# 48-24.net
KiCad netlist of a schematic drawn in EasyEDA Pro
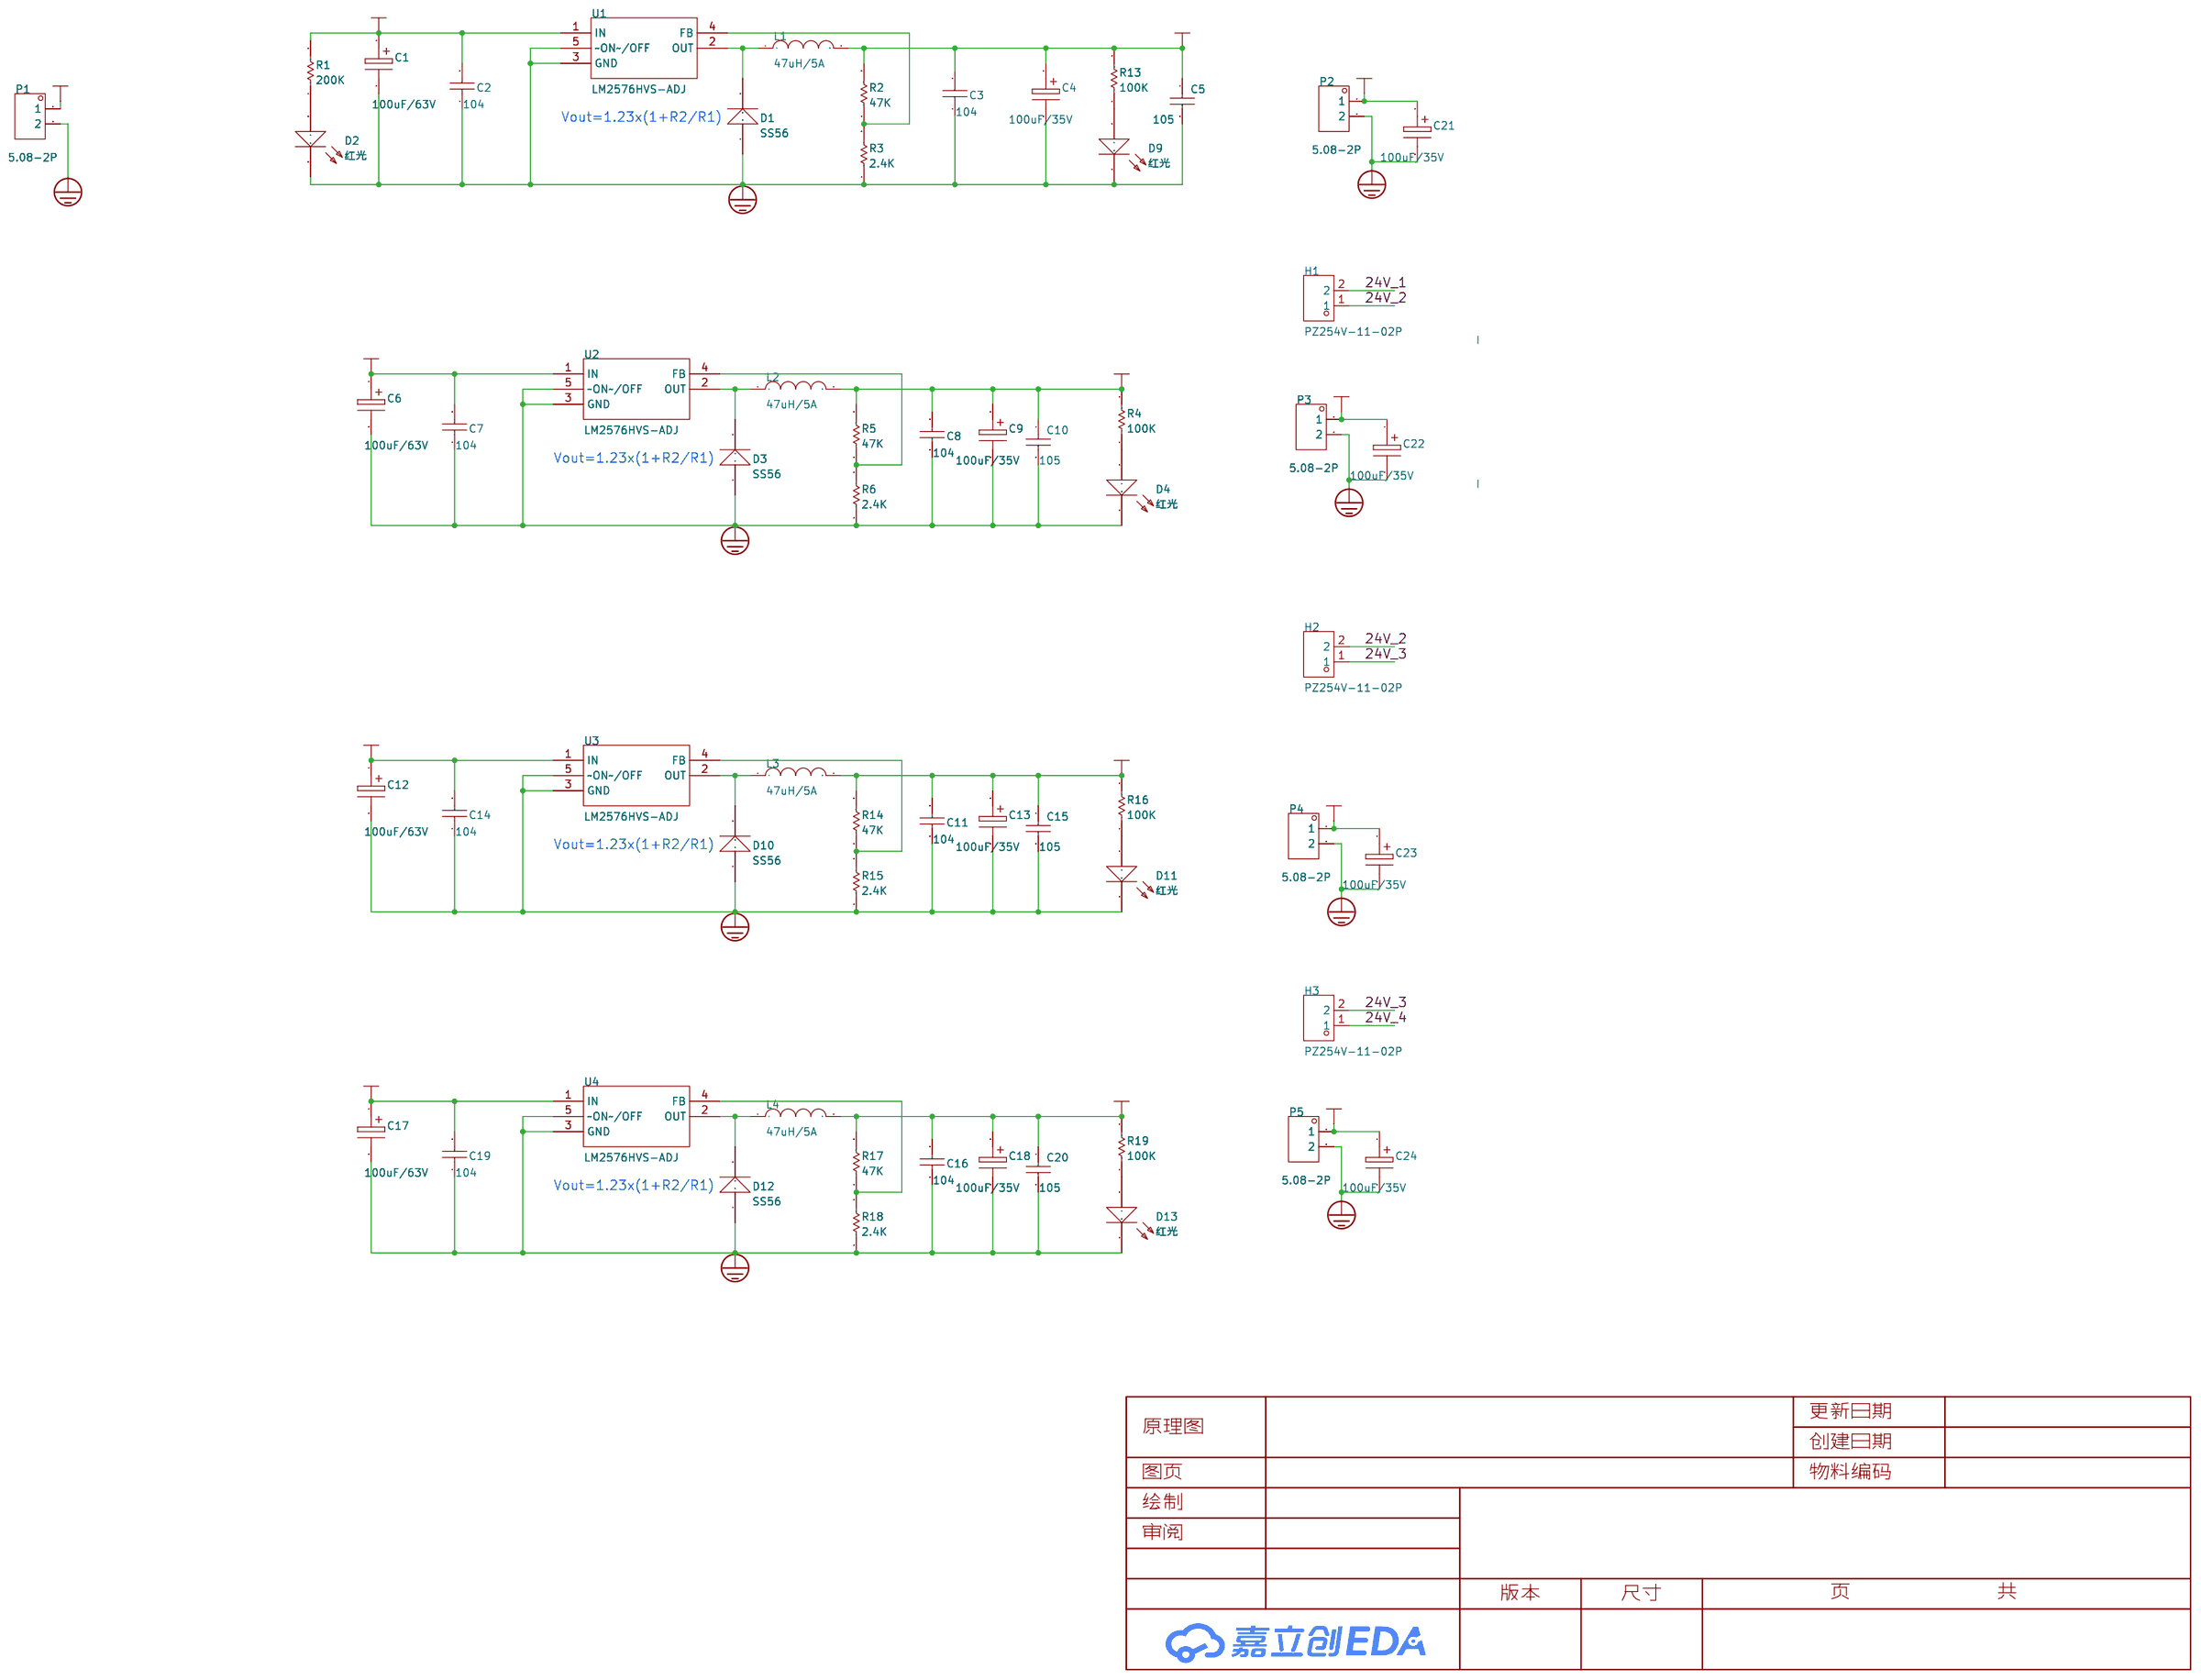
[diagram p0: schematic sheet]

(export (version "E")
  (design (tool "Eeschema 10.0.6"))
  (components
    (comp (ref "C1")
      (value "100uF/63V")
      (footprint "easyedapro:电解电容贴片10x10")
      (libsource (lib "easyedapro") (part "ELECTRO1"))
    )
    (comp (ref "C2")
      (value "104")
      (footprint "easyedapro:电解电容贴片6X6")
      (libsource (lib "easyedapro") (part "CAP"))
    )
    (comp (ref "C3")
      (value "104")
      (footprint "easyedapro:电解电容贴片6X6")
      (libsource (lib "easyedapro") (part "CAP"))
    )
    (comp (ref "C4")
      (value "100uF/35V")
      (footprint "easyedapro:电解电容贴片10x10")
      (libsource (lib "easyedapro") (part "ELECTRO1"))
    )
    (comp (ref "C5")
      (value "105")
      (footprint "easyedapro:电解电容贴片6X6")
      (libsource (lib "easyedapro") (part "CAP"))
    )
    (comp (ref "C6")
      (value "100uF/63V")
      (footprint "easyedapro:电解电容贴片10x10")
      (libsource (lib "easyedapro") (part "ELECTRO1"))
    )
    (comp (ref "C7")
      (value "104")
      (footprint "easyedapro:电解电容贴片6X6")
      (libsource (lib "easyedapro") (part "CAP"))
    )
    (comp (ref "C8")
      (value "104")
      (footprint "easyedapro:电解电容贴片6X6")
      (libsource (lib "easyedapro") (part "CAP"))
    )
    (comp (ref "C9")
      (value "100uF/35V")
      (footprint "easyedapro:电解电容贴片10x10")
      (libsource (lib "easyedapro") (part "ELECTRO1"))
    )
    (comp (ref "C10")
      (value "105")
      (footprint "easyedapro:电解电容贴片6X6")
      (libsource (lib "easyedapro") (part "CAP"))
    )
    (comp (ref "C11")
      (value "104")
      (footprint "easyedapro:电解电容贴片6X6")
      (libsource (lib "easyedapro") (part "CAP"))
    )
    (comp (ref "C12")
      (value "100uF/63V")
      (footprint "easyedapro:电解电容贴片10x10")
      (libsource (lib "easyedapro") (part "ELECTRO1"))
    )
    (comp (ref "C13")
      (value "100uF/35V")
      (footprint "easyedapro:电解电容贴片10x10")
      (libsource (lib "easyedapro") (part "ELECTRO1"))
    )
    (comp (ref "C14")
      (value "104")
      (footprint "easyedapro:电解电容贴片6X6")
      (libsource (lib "easyedapro") (part "CAP"))
    )
    (comp (ref "C15")
      (value "105")
      (footprint "easyedapro:电解电容贴片6X6")
      (libsource (lib "easyedapro") (part "CAP"))
    )
    (comp (ref "C16")
      (value "104")
      (footprint "easyedapro:电解电容贴片6X6")
      (libsource (lib "easyedapro") (part "CAP"))
    )
    (comp (ref "C17")
      (value "100uF/63V")
      (footprint "easyedapro:电解电容贴片10x10")
      (libsource (lib "easyedapro") (part "ELECTRO1"))
    )
    (comp (ref "C18")
      (value "100uF/35V")
      (footprint "easyedapro:电解电容贴片10x10")
      (libsource (lib "easyedapro") (part "ELECTRO1"))
    )
    (comp (ref "C19")
      (value "104")
      (footprint "easyedapro:电解电容贴片6X6")
      (libsource (lib "easyedapro") (part "CAP"))
    )
    (comp (ref "C20")
      (value "105")
      (footprint "easyedapro:电解电容贴片6X6")
      (libsource (lib "easyedapro") (part "CAP"))
    )
    (comp (ref "C21")
      (value "100uF/35V")
      (footprint "easyedapro:电解电容贴片10x10")
      (libsource (lib "easyedapro") (part "ELECTRO1"))
    )
    (comp (ref "C22")
      (value "100uF/35V")
      (footprint "easyedapro:电解电容贴片10x10")
      (libsource (lib "easyedapro") (part "ELECTRO1"))
    )
    (comp (ref "C23")
      (value "100uF/35V")
      (footprint "easyedapro:电解电容贴片10x10")
      (libsource (lib "easyedapro") (part "ELECTRO1"))
    )
    (comp (ref "C24")
      (value "100uF/35V")
      (footprint "easyedapro:电解电容贴片10x10")
      (libsource (lib "easyedapro") (part "ELECTRO1"))
    )
    (comp (ref "D1")
      (value "SS56")
      (footprint "easyedapro:SMA")
      (libsource (lib "easyedapro") (part "1N4148"))
    )
    (comp (ref "D2")
      (value "红光")
      (footprint "easyedapro:0603LED")
      (libsource (lib "easyedapro") (part "LED"))
    )
    (comp (ref "D3")
      (value "SS56")
      (footprint "easyedapro:SMA")
      (libsource (lib "easyedapro") (part "1N4148"))
    )
    (comp (ref "D4")
      (value "红光")
      (footprint "easyedapro:0603LED")
      (libsource (lib "easyedapro") (part "LED"))
    )
    (comp (ref "D9")
      (value "红光")
      (footprint "easyedapro:0603LED")
      (libsource (lib "easyedapro") (part "LED"))
    )
    (comp (ref "D10")
      (value "SS56")
      (footprint "easyedapro:SMA")
      (libsource (lib "easyedapro") (part "1N4148"))
    )
    (comp (ref "D11")
      (value "红光")
      (footprint "easyedapro:0603LED")
      (libsource (lib "easyedapro") (part "LED"))
    )
    (comp (ref "D12")
      (value "SS56")
      (footprint "easyedapro:SMA")
      (libsource (lib "easyedapro") (part "1N4148"))
    )
    (comp (ref "D13")
      (value "红光")
      (footprint "easyedapro:0603LED")
      (libsource (lib "easyedapro") (part "LED"))
    )
    (comp (ref "H1")
      (value "PZ254V-11-02P")
      (footprint "easyedapro:HDR-TH_2P-P2.54-V-M")
      (fields (field (name "Manufacturer") "XFCN(兴飞)"))
      (libsource (lib "easyedapro") (part "PZ254V-11-02P"))
    )
    (comp (ref "H2")
      (value "PZ254V-11-02P")
      (footprint "easyedapro:HDR-TH_2P-P2.54-V-M")
      (fields (field (name "Manufacturer") "XFCN(兴飞)"))
      (libsource (lib "easyedapro") (part "PZ254V-11-02P"))
    )
    (comp (ref "H3")
      (value "PZ254V-11-02P")
      (footprint "easyedapro:HDR-TH_2P-P2.54-V-M")
      (fields (field (name "Manufacturer") "XFCN(兴飞)"))
      (libsource (lib "easyedapro") (part "PZ254V-11-02P"))
    )
    (comp (ref "L1")
      (value "47uH/5A")
      (footprint "easyedapro:IND-SMD_L13.45-W12.6")
      (description "Inductor")
      (libsource (lib "easyedapro") (part "Inductor"))
    )
    (comp (ref "L2")
      (value "47uH/5A")
      (footprint "easyedapro:IND-SMD_L13.45-W12.6")
      (description "Inductor")
      (libsource (lib "easyedapro") (part "Inductor"))
    )
    (comp (ref "L3")
      (value "47uH/5A")
      (footprint "easyedapro:IND-SMD_L13.45-W12.6")
      (description "Inductor")
      (libsource (lib "easyedapro") (part "Inductor"))
    )
    (comp (ref "L4")
      (value "47uH/5A")
      (footprint "easyedapro:IND-SMD_L13.45-W12.6")
      (description "Inductor")
      (libsource (lib "easyedapro") (part "Inductor"))
    )
    (comp (ref "P1")
      (value "5.08-2P")
      (footprint "easyedapro:CONN-TH_WJ2EDGVC-5.08-2P")
      (fields (field (name "Manufacturer") "KANGNEX(康奈克斯电气)"))
      (libsource (lib "easyedapro") (part "WJ2EDGVC-5.08-2P"))
    )
    (comp (ref "P2")
      (value "5.08-2P")
      (footprint "easyedapro:CONN-TH_WJ2EDGVC-5.08-2P")
      (fields (field (name "Manufacturer") "KANGNEX(康奈克斯电气)"))
      (libsource (lib "easyedapro") (part "WJ2EDGVC-5.08-2P"))
    )
    (comp (ref "P3")
      (value "5.08-2P")
      (footprint "easyedapro:CONN-TH_WJ2EDGVC-5.08-2P")
      (fields (field (name "Manufacturer") "KANGNEX(康奈克斯电气)"))
      (libsource (lib "easyedapro") (part "WJ2EDGVC-5.08-2P"))
    )
    (comp (ref "P4")
      (value "5.08-2P")
      (footprint "easyedapro:CONN-TH_WJ2EDGVC-5.08-2P")
      (fields (field (name "Manufacturer") "KANGNEX(康奈克斯电气)"))
      (libsource (lib "easyedapro") (part "WJ2EDGVC-5.08-2P"))
    )
    (comp (ref "P5")
      (value "5.08-2P")
      (footprint "easyedapro:CONN-TH_WJ2EDGVC-5.08-2P")
      (fields (field (name "Manufacturer") "KANGNEX(康奈克斯电气)"))
      (libsource (lib "easyedapro") (part "WJ2EDGVC-5.08-2P"))
    )
    (comp (ref "R1")
      (value "10K")
      (footprint "easyedapro:0603R")
      (description "Resistor")
      (libsource (lib "easyedapro") (part "RES"))
    )
    (comp (ref "R2")
      (value "47K")
      (footprint "easyedapro:0603R")
      (description "Resistor")
      (libsource (lib "easyedapro") (part "RES"))
    )
    (comp (ref "R3")
      (value "2.4K")
      (footprint "easyedapro:0603R")
      (description "Resistor")
      (libsource (lib "easyedapro") (part "RES"))
    )
    (comp (ref "R4")
      (value "10K")
      (footprint "easyedapro:0603R")
      (description "Resistor")
      (libsource (lib "easyedapro") (part "RES"))
    )
    (comp (ref "R5")
      (value "47K")
      (footprint "easyedapro:0603R")
      (description "Resistor")
      (libsource (lib "easyedapro") (part "RES"))
    )
    (comp (ref "R6")
      (value "2.4K")
      (footprint "easyedapro:0603R")
      (description "Resistor")
      (libsource (lib "easyedapro") (part "RES"))
    )
    (comp (ref "R13")
      (value "10K")
      (footprint "easyedapro:0603R")
      (description "Resistor")
      (libsource (lib "easyedapro") (part "RES"))
    )
    (comp (ref "R14")
      (value "47K")
      (footprint "easyedapro:0603R")
      (description "Resistor")
      (libsource (lib "easyedapro") (part "RES"))
    )
    (comp (ref "R15")
      (value "2.4K")
      (footprint "easyedapro:0603R")
      (description "Resistor")
      (libsource (lib "easyedapro") (part "RES"))
    )
    (comp (ref "R16")
      (value "10K")
      (footprint "easyedapro:0603R")
      (description "Resistor")
      (libsource (lib "easyedapro") (part "RES"))
    )
    (comp (ref "R17")
      (value "47K")
      (footprint "easyedapro:0603R")
      (description "Resistor")
      (libsource (lib "easyedapro") (part "RES"))
    )
    (comp (ref "R18")
      (value "2.4K")
      (footprint "easyedapro:0603R")
      (description "Resistor")
      (libsource (lib "easyedapro") (part "RES"))
    )
    (comp (ref "R19")
      (value "10K")
      (footprint "easyedapro:0603R")
      (description "Resistor")
      (libsource (lib "easyedapro") (part "RES"))
    )
    (comp (ref "U1")
      (value "LM2576HVS-ADJ")
      (footprint "easyedapro:TO-263")
      (description "Simple Switcher 3A Step Down Voltage Regulator")
      (libsource (lib "easyedapro") (part "LM2576S-5.0"))
    )
    (comp (ref "U2")
      (value "LM2576HVS-ADJ")
      (footprint "easyedapro:TO-263")
      (description "Simple Switcher 3A Step Down Voltage Regulator")
      (libsource (lib "easyedapro") (part "LM2576S-5.0"))
    )
    (comp (ref "U3")
      (value "LM2576HVS-ADJ")
      (footprint "easyedapro:TO-263")
      (description "Simple Switcher 3A Step Down Voltage Regulator")
      (libsource (lib "easyedapro") (part "LM2576S-5.0"))
    )
    (comp (ref "U4")
      (value "LM2576HVS-ADJ")
      (footprint "easyedapro:TO-263")
      (description "Simple Switcher 3A Step Down Voltage Regulator")
      (libsource (lib "easyedapro") (part "LM2576S-5.0"))
    )
  )
  (nets
    (net (code "1") (name "24V_1") (class "Default")
      (node (ref "C21") (pin "1") (pintype "unspecified"))
      (node (ref "C3") (pin "2") (pinfunction "2_2") (pintype "unspecified"))
      (node (ref "C4") (pin "1") (pintype "unspecified"))
      (node (ref "C5") (pin "1") (pinfunction "1_1") (pintype "unspecified"))
      (node (ref "H1") (pin "2") (pinfunction "2_2") (pintype "unspecified"))
      (node (ref "L1") (pin "2") (pinfunction "2_2") (pintype "unspecified"))
      (node (ref "P2") (pin "1") (pinfunction "1_1") (pintype "unspecified"))
      (node (ref "R13") (pin "2") (pinfunction "2_2") (pintype "unspecified"))
      (node (ref "R2") (pin "2") (pinfunction "2_2") (pintype "unspecified"))
    )
    (net (code "2") (name "24V_2") (class "Default")
      (node (ref "C10") (pin "1") (pinfunction "1_1") (pintype "unspecified"))
      (node (ref "C22") (pin "1") (pintype "unspecified"))
      (node (ref "C8") (pin "2") (pinfunction "2_2") (pintype "unspecified"))
      (node (ref "C9") (pin "1") (pintype "unspecified"))
      (node (ref "H1") (pin "1") (pinfunction "1_1") (pintype "unspecified"))
      (node (ref "H2") (pin "2") (pinfunction "2_2") (pintype "unspecified"))
      (node (ref "L2") (pin "2") (pinfunction "2_2") (pintype "unspecified"))
      (node (ref "P3") (pin "1") (pinfunction "1_1") (pintype "unspecified"))
      (node (ref "R4") (pin "2") (pinfunction "2_2") (pintype "unspecified"))
      (node (ref "R5") (pin "2") (pinfunction "2_2") (pintype "unspecified"))
    )
    (net (code "3") (name "24V_3") (class "Default")
      (node (ref "C11") (pin "2") (pinfunction "2_2") (pintype "unspecified"))
      (node (ref "C13") (pin "1") (pintype "unspecified"))
      (node (ref "C15") (pin "1") (pinfunction "1_1") (pintype "unspecified"))
      (node (ref "C23") (pin "1") (pintype "unspecified"))
      (node (ref "H2") (pin "1") (pinfunction "1_1") (pintype "unspecified"))
      (node (ref "H3") (pin "2") (pinfunction "2_2") (pintype "unspecified"))
      (node (ref "L3") (pin "2") (pinfunction "2_2") (pintype "unspecified"))
      (node (ref "P4") (pin "1") (pinfunction "1_1") (pintype "unspecified"))
      (node (ref "R14") (pin "2") (pinfunction "2_2") (pintype "unspecified"))
      (node (ref "R16") (pin "2") (pinfunction "2_2") (pintype "unspecified"))
    )
    (net (code "4") (name "24V_4") (class "Default")
      (node (ref "C16") (pin "2") (pinfunction "2_2") (pintype "unspecified"))
      (node (ref "C18") (pin "1") (pintype "unspecified"))
      (node (ref "C20") (pin "1") (pinfunction "1_1") (pintype "unspecified"))
      (node (ref "C24") (pin "1") (pintype "unspecified"))
      (node (ref "H3") (pin "1") (pinfunction "1_1") (pintype "unspecified"))
      (node (ref "L4") (pin "2") (pinfunction "2_2") (pintype "unspecified"))
      (node (ref "P5") (pin "1") (pinfunction "1_1") (pintype "unspecified"))
      (node (ref "R17") (pin "2") (pinfunction "2_2") (pintype "unspecified"))
      (node (ref "R19") (pin "2") (pinfunction "2_2") (pintype "unspecified"))
    )
    (net (code "5") (name "48V_IN") (class "Default")
      (node (ref "C1") (pin "1") (pintype "unspecified"))
      (node (ref "C12") (pin "1") (pintype "unspecified"))
      (node (ref "C14") (pin "2") (pinfunction "2_2") (pintype "unspecified"))
      (node (ref "C17") (pin "1") (pintype "unspecified"))
      (node (ref "C19") (pin "2") (pinfunction "2_2") (pintype "unspecified"))
      (node (ref "C2") (pin "2") (pinfunction "2_2") (pintype "unspecified"))
      (node (ref "C6") (pin "1") (pintype "unspecified"))
      (node (ref "C7") (pin "2") (pinfunction "2_2") (pintype "unspecified"))
      (node (ref "P1") (pin "1") (pinfunction "1_1") (pintype "unspecified"))
      (node (ref "R1") (pin "2") (pinfunction "2_2") (pintype "unspecified"))
      (node (ref "U1") (pin "1") (pinfunction "IN_1") (pintype "unspecified"))
      (node (ref "U2") (pin "1") (pinfunction "IN_1") (pintype "unspecified"))
      (node (ref "U3") (pin "1") (pinfunction "IN_1") (pintype "unspecified"))
      (node (ref "U4") (pin "1") (pinfunction "IN_1") (pintype "unspecified"))
    )
    (net (code "6") (name "GND") (class "Default")
      (node (ref "C1") (pin "2") (pintype "unspecified"))
      (node (ref "C10") (pin "2") (pinfunction "2_2") (pintype "unspecified"))
      (node (ref "C11") (pin "1") (pinfunction "1_1") (pintype "unspecified"))
      (node (ref "C12") (pin "2") (pintype "unspecified"))
      (node (ref "C13") (pin "2") (pintype "unspecified"))
      (node (ref "C14") (pin "1") (pinfunction "1_1") (pintype "unspecified"))
      (node (ref "C15") (pin "2") (pinfunction "2_2") (pintype "unspecified"))
      (node (ref "C16") (pin "1") (pinfunction "1_1") (pintype "unspecified"))
      (node (ref "C17") (pin "2") (pintype "unspecified"))
      (node (ref "C18") (pin "2") (pintype "unspecified"))
      (node (ref "C19") (pin "1") (pinfunction "1_1") (pintype "unspecified"))
      (node (ref "C2") (pin "1") (pinfunction "1_1") (pintype "unspecified"))
      (node (ref "C20") (pin "2") (pinfunction "2_2") (pintype "unspecified"))
      (node (ref "C21") (pin "2") (pintype "unspecified"))
      (node (ref "C22") (pin "2") (pintype "unspecified"))
      (node (ref "C23") (pin "2") (pintype "unspecified"))
      (node (ref "C24") (pin "2") (pintype "unspecified"))
      (node (ref "C3") (pin "1") (pinfunction "1_1") (pintype "unspecified"))
      (node (ref "C4") (pin "2") (pintype "unspecified"))
      (node (ref "C5") (pin "2") (pinfunction "2_2") (pintype "unspecified"))
      (node (ref "C6") (pin "2") (pintype "unspecified"))
      (node (ref "C7") (pin "1") (pinfunction "1_1") (pintype "unspecified"))
      (node (ref "C8") (pin "1") (pinfunction "1_1") (pintype "unspecified"))
      (node (ref "C9") (pin "2") (pintype "unspecified"))
      (node (ref "D1") (pin "1") (pinfunction "1_1") (pintype "unspecified"))
      (node (ref "D10") (pin "1") (pinfunction "1_1") (pintype "unspecified"))
      (node (ref "D11") (pin "2") (pinfunction "2_2") (pintype "unspecified"))
      (node (ref "D12") (pin "1") (pinfunction "1_1") (pintype "unspecified"))
      (node (ref "D13") (pin "2") (pinfunction "2_2") (pintype "unspecified"))
      (node (ref "D2") (pin "2") (pinfunction "2_2") (pintype "unspecified"))
      (node (ref "D3") (pin "1") (pinfunction "1_1") (pintype "unspecified"))
      (node (ref "D4") (pin "2") (pinfunction "2_2") (pintype "unspecified"))
      (node (ref "D9") (pin "2") (pinfunction "2_2") (pintype "unspecified"))
      (node (ref "P1") (pin "2") (pinfunction "2_2") (pintype "unspecified"))
      (node (ref "P2") (pin "2") (pinfunction "2_2") (pintype "unspecified"))
      (node (ref "P3") (pin "2") (pinfunction "2_2") (pintype "unspecified"))
      (node (ref "P4") (pin "2") (pinfunction "2_2") (pintype "unspecified"))
      (node (ref "P5") (pin "2") (pinfunction "2_2") (pintype "unspecified"))
      (node (ref "R15") (pin "1") (pinfunction "1_1") (pintype "unspecified"))
      (node (ref "R18") (pin "1") (pinfunction "1_1") (pintype "unspecified"))
      (node (ref "R3") (pin "1") (pinfunction "1_1") (pintype "unspecified"))
      (node (ref "R6") (pin "1") (pinfunction "1_1") (pintype "unspecified"))
      (node (ref "U1") (pin "3") (pinfunction "GND_3") (pintype "unspecified"))
      (node (ref "U1") (pin "5") (pinfunction "~ON~/OFF_5") (pintype "input"))
      (node (ref "U2") (pin "3") (pinfunction "GND_3") (pintype "unspecified"))
      (node (ref "U2") (pin "5") (pinfunction "~ON~/OFF_5") (pintype "input"))
      (node (ref "U3") (pin "3") (pinfunction "GND_3") (pintype "unspecified"))
      (node (ref "U3") (pin "5") (pinfunction "~ON~/OFF_5") (pintype "input"))
      (node (ref "U4") (pin "3") (pinfunction "GND_3") (pintype "unspecified"))
      (node (ref "U4") (pin "5") (pinfunction "~ON~/OFF_5") (pintype "input"))
    )
    (net (code "7") (name "Net-(D2-Pad1)") (class "Default")
      (node (ref "D2") (pin "1") (pinfunction "1_1") (pintype "unspecified"))
      (node (ref "R1") (pin "1") (pinfunction "1_1") (pintype "unspecified"))
    )
    (net (code "8") (name "Net-(D4-Pad1)") (class "Default")
      (node (ref "D4") (pin "1") (pinfunction "1_1") (pintype "unspecified"))
      (node (ref "R4") (pin "1") (pinfunction "1_1") (pintype "unspecified"))
    )
    (net (code "9") (name "Net-(D9-Pad1)") (class "Default")
      (node (ref "D9") (pin "1") (pinfunction "1_1") (pintype "unspecified"))
      (node (ref "R13") (pin "1") (pinfunction "1_1") (pintype "unspecified"))
    )
    (net (code "10") (name "Net-(D11-Pad1)") (class "Default")
      (node (ref "D11") (pin "1") (pinfunction "1_1") (pintype "unspecified"))
      (node (ref "R16") (pin "1") (pinfunction "1_1") (pintype "unspecified"))
    )
    (net (code "11") (name "Net-(D13-Pad1)") (class "Default")
      (node (ref "D13") (pin "1") (pinfunction "1_1") (pintype "unspecified"))
      (node (ref "R19") (pin "1") (pinfunction "1_1") (pintype "unspecified"))
    )
    (net (code "12") (name "Net-(U1-FB)") (class "Default")
      (node (ref "R2") (pin "1") (pinfunction "1_1") (pintype "unspecified"))
      (node (ref "R3") (pin "2") (pinfunction "2_2") (pintype "unspecified"))
      (node (ref "U1") (pin "4") (pinfunction "FB_4") (pintype "input"))
    )
    (net (code "13") (name "Net-(U1-OUT)") (class "Default")
      (node (ref "D1") (pin "2") (pinfunction "2_2") (pintype "unspecified"))
      (node (ref "L1") (pin "1") (pinfunction "1_1") (pintype "unspecified"))
      (node (ref "U1") (pin "2") (pinfunction "OUT_2") (pintype "unspecified"))
    )
    (net (code "14") (name "Net-(U2-FB)") (class "Default")
      (node (ref "R5") (pin "1") (pinfunction "1_1") (pintype "unspecified"))
      (node (ref "R6") (pin "2") (pinfunction "2_2") (pintype "unspecified"))
      (node (ref "U2") (pin "4") (pinfunction "FB_4") (pintype "input"))
    )
    (net (code "15") (name "Net-(U2-OUT)") (class "Default")
      (node (ref "D3") (pin "2") (pinfunction "2_2") (pintype "unspecified"))
      (node (ref "L2") (pin "1") (pinfunction "1_1") (pintype "unspecified"))
      (node (ref "U2") (pin "2") (pinfunction "OUT_2") (pintype "unspecified"))
    )
    (net (code "16") (name "Net-(U3-FB)") (class "Default")
      (node (ref "R14") (pin "1") (pinfunction "1_1") (pintype "unspecified"))
      (node (ref "R15") (pin "2") (pinfunction "2_2") (pintype "unspecified"))
      (node (ref "U3") (pin "4") (pinfunction "FB_4") (pintype "input"))
    )
    (net (code "17") (name "Net-(U3-OUT)") (class "Default")
      (node (ref "D10") (pin "2") (pinfunction "2_2") (pintype "unspecified"))
      (node (ref "L3") (pin "1") (pinfunction "1_1") (pintype "unspecified"))
      (node (ref "U3") (pin "2") (pinfunction "OUT_2") (pintype "unspecified"))
    )
    (net (code "18") (name "Net-(U4-FB)") (class "Default")
      (node (ref "R17") (pin "1") (pinfunction "1_1") (pintype "unspecified"))
      (node (ref "R18") (pin "2") (pinfunction "2_2") (pintype "unspecified"))
      (node (ref "U4") (pin "4") (pinfunction "FB_4") (pintype "input"))
    )
    (net (code "19") (name "Net-(U4-OUT)") (class "Default")
      (node (ref "D12") (pin "2") (pinfunction "2_2") (pintype "unspecified"))
      (node (ref "L4") (pin "1") (pinfunction "1_1") (pintype "unspecified"))
      (node (ref "U4") (pin "2") (pinfunction "OUT_2") (pintype "unspecified"))
    )
  )
)
